# Single_Board_12s_baru_v2.net
KiCad netlist of a schematic drawn in EAGLE
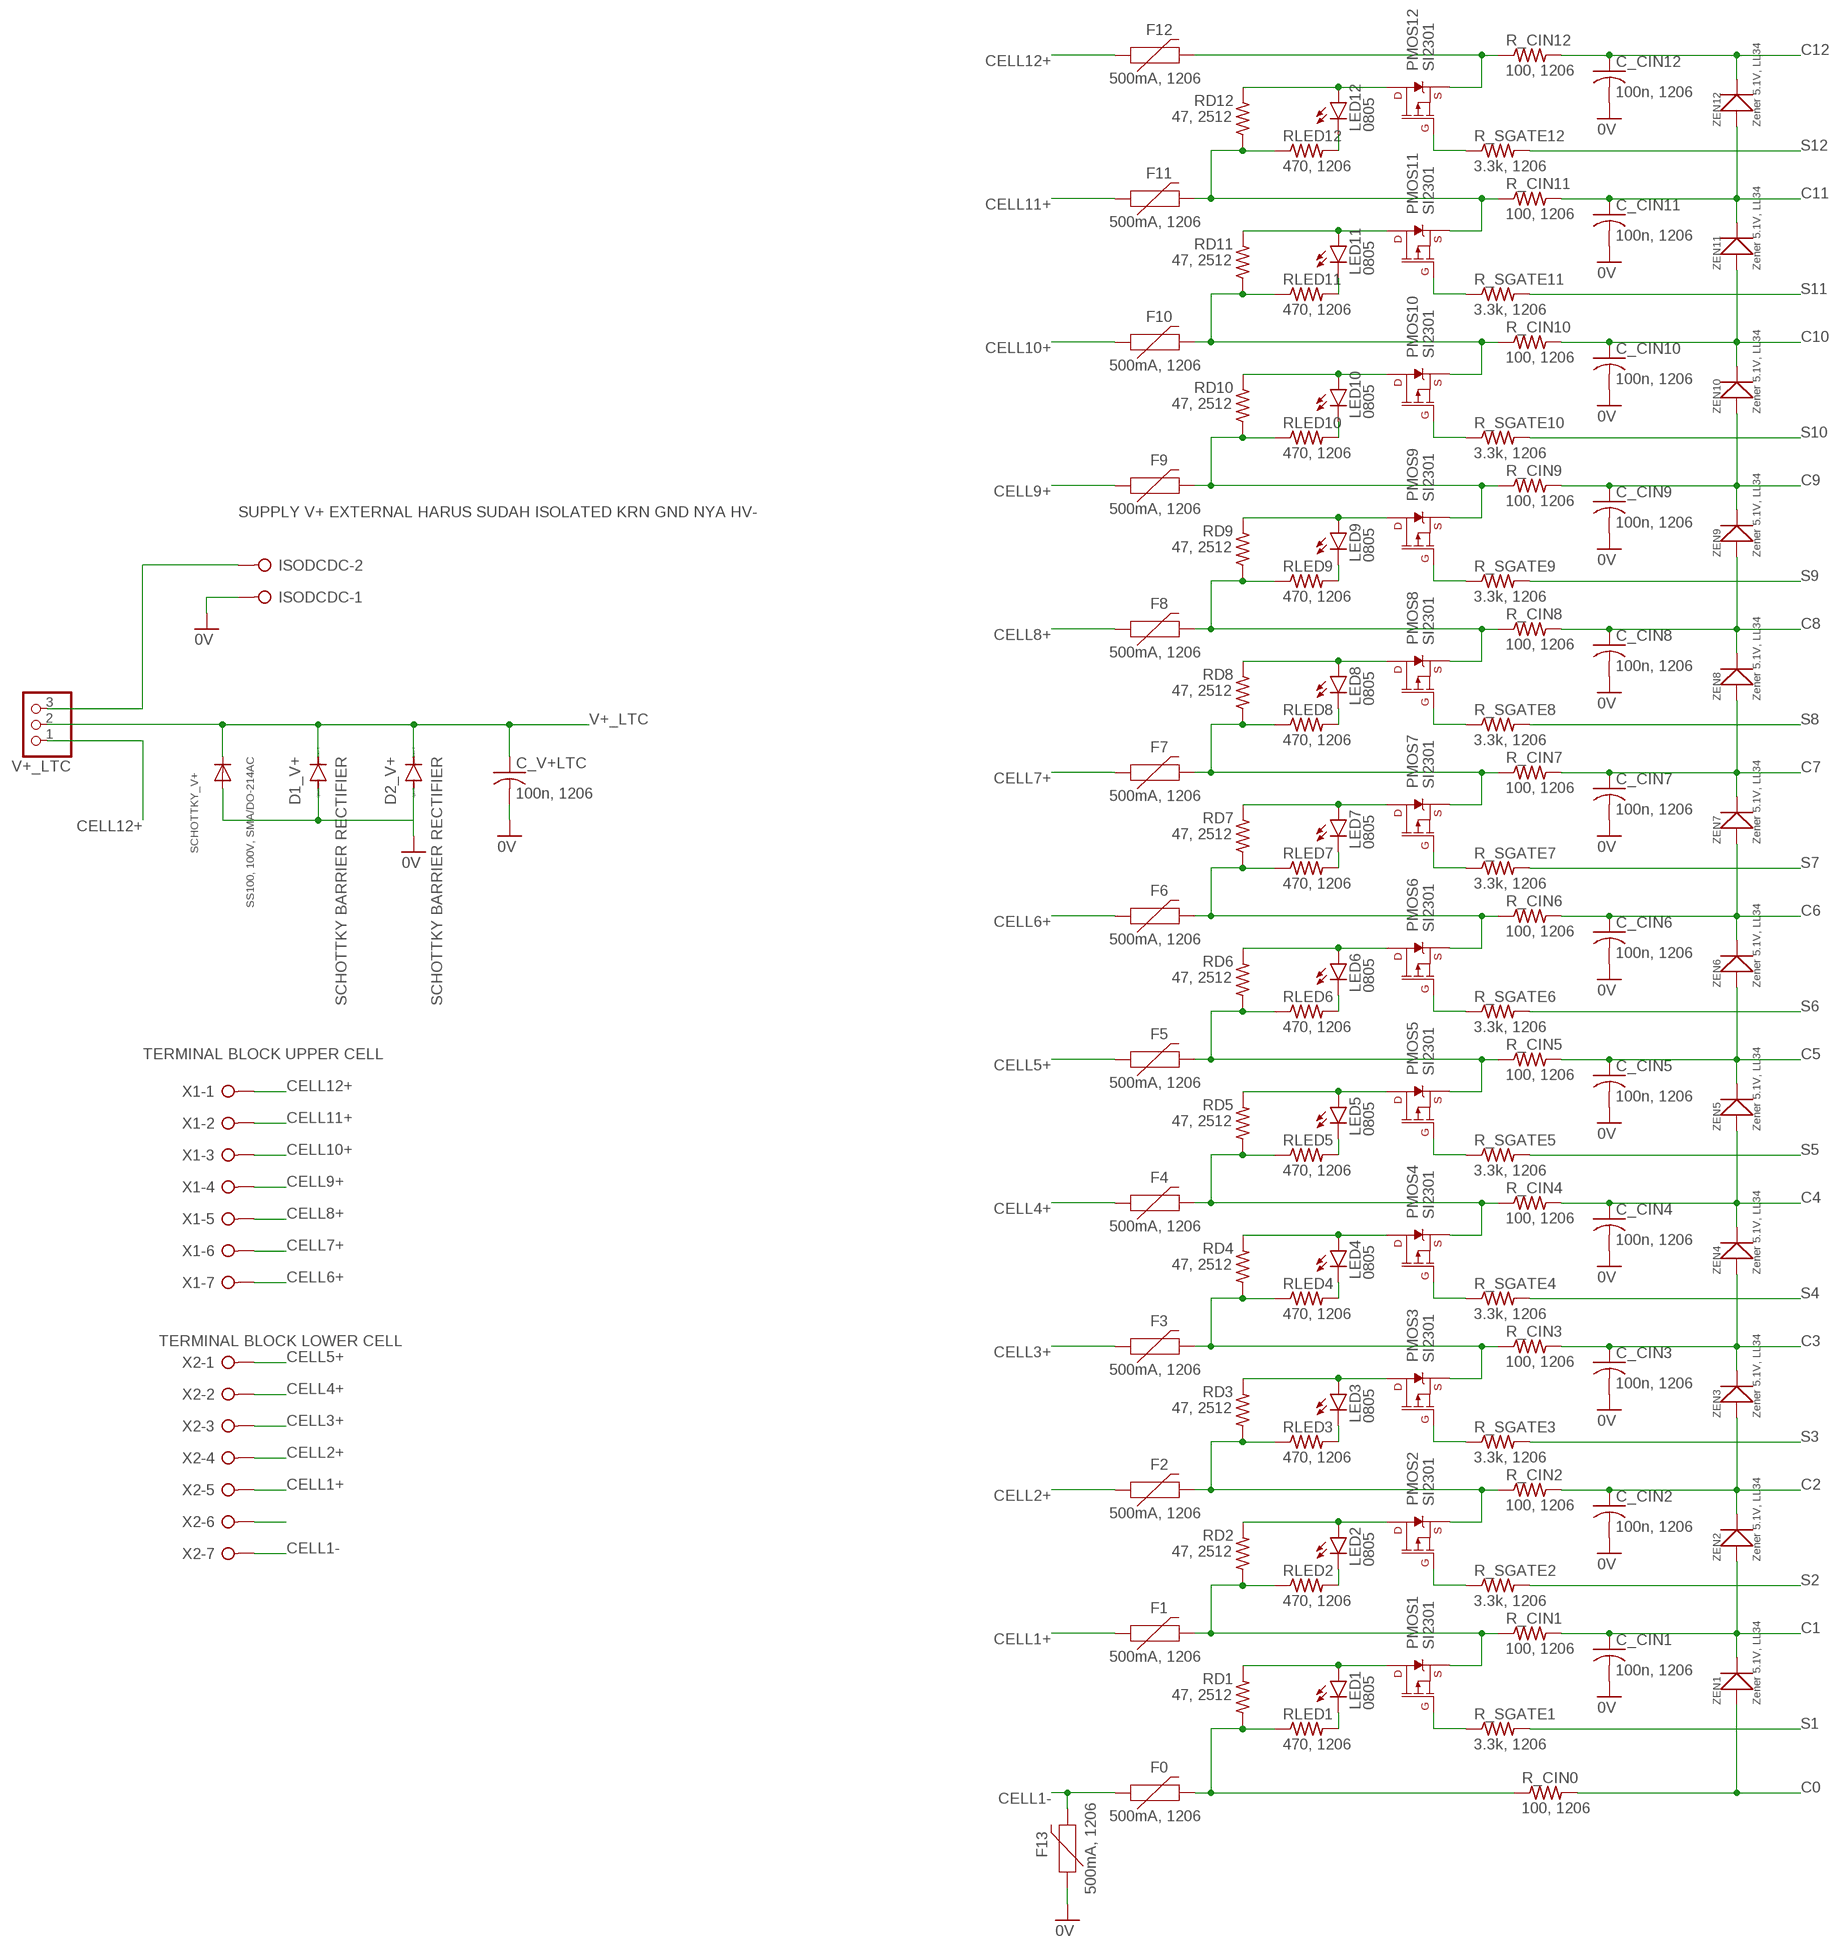
[diagram p0: schematic, sheet 1, part 1 of 2]
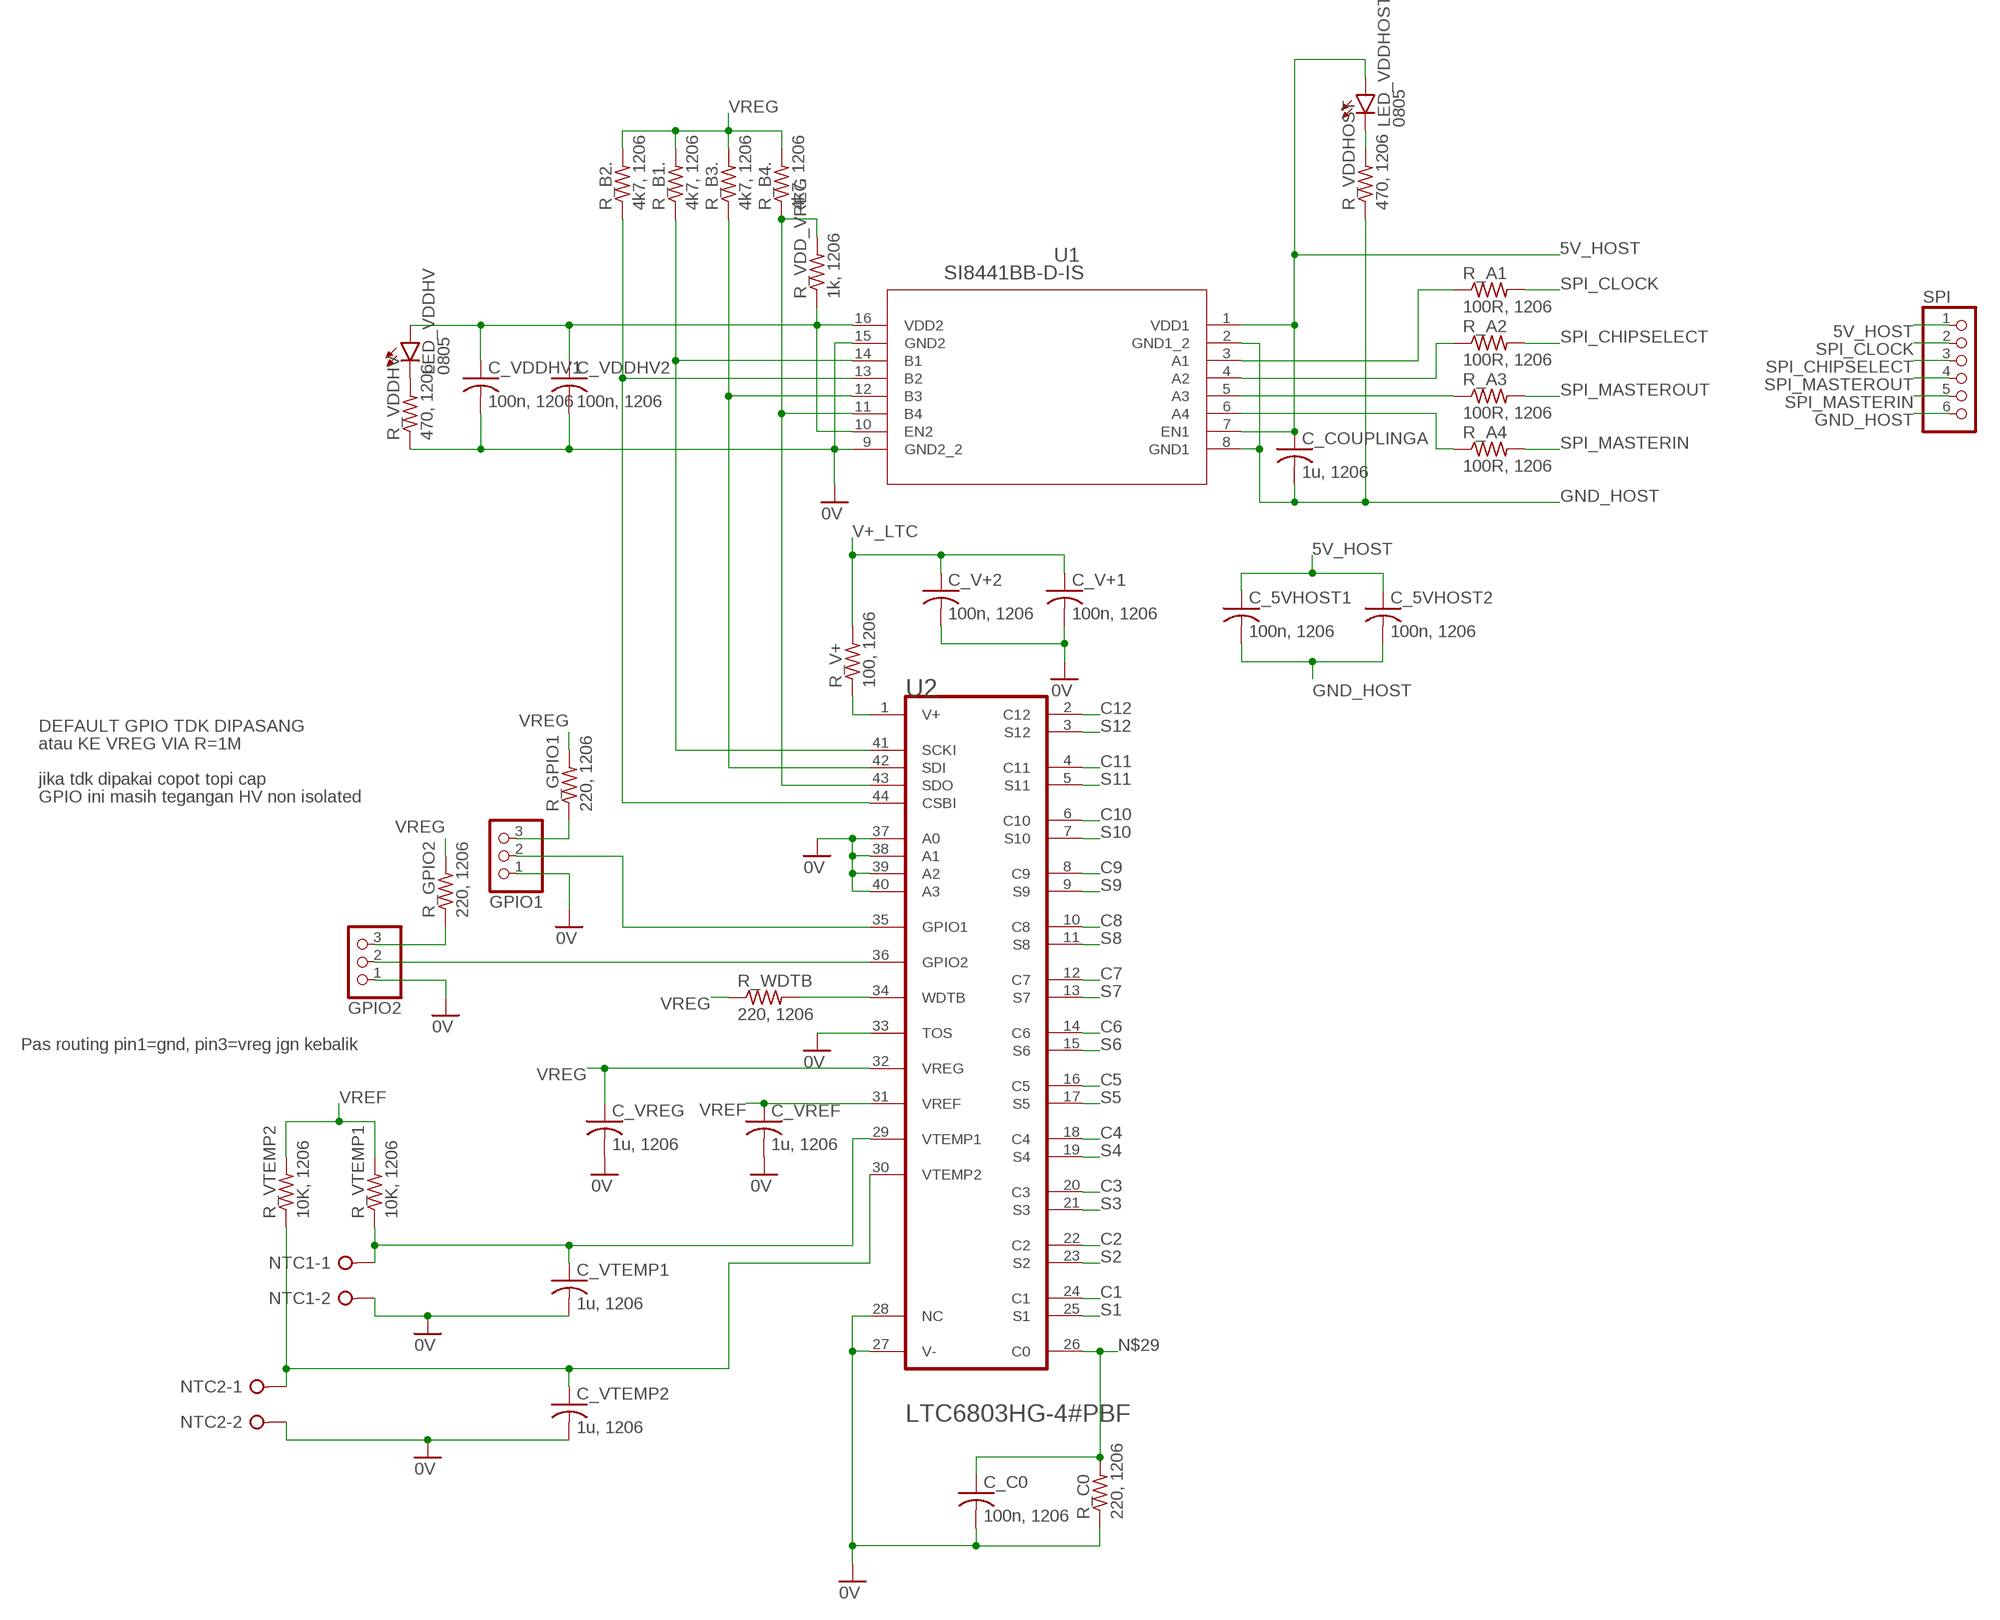
[diagram p1: schematic, sheet 1, part 2 of 2]

(export (version "E")
  (design (tool "Eeschema 10.0.6"))
  (components
    (comp (ref "C_5VHOST1")
      (value "100n, 1206")
      (footprint "eagle-import:C1206")
      (libsource (lib "eagle-import") (part "C-USC1206"))
    )
    (comp (ref "C_5VHOST2")
      (value "100n, 1206")
      (footprint "eagle-import:C1206")
      (libsource (lib "eagle-import") (part "C-USC1206"))
    )
    (comp (ref "C_C0")
      (value "100n, 1206")
      (footprint "eagle-import:C1206")
      (libsource (lib "eagle-import") (part "C-USC1206"))
    )
    (comp (ref "C_CIN1")
      (value "100n, 1206")
      (footprint "eagle-import:C1206")
      (libsource (lib "eagle-import") (part "C-USC1206"))
    )
    (comp (ref "C_CIN2")
      (value "100n, 1206")
      (footprint "eagle-import:C1206")
      (libsource (lib "eagle-import") (part "C-USC1206"))
    )
    (comp (ref "C_CIN3")
      (value "100n, 1206")
      (footprint "eagle-import:C1206")
      (libsource (lib "eagle-import") (part "C-USC1206"))
    )
    (comp (ref "C_CIN4")
      (value "100n, 1206")
      (footprint "eagle-import:C1206")
      (libsource (lib "eagle-import") (part "C-USC1206"))
    )
    (comp (ref "C_CIN5")
      (value "100n, 1206")
      (footprint "eagle-import:C1206")
      (libsource (lib "eagle-import") (part "C-USC1206"))
    )
    (comp (ref "C_CIN6")
      (value "100n, 1206")
      (footprint "eagle-import:C1206")
      (libsource (lib "eagle-import") (part "C-USC1206"))
    )
    (comp (ref "C_CIN7")
      (value "100n, 1206")
      (footprint "eagle-import:C1206")
      (libsource (lib "eagle-import") (part "C-USC1206"))
    )
    (comp (ref "C_CIN8")
      (value "100n, 1206")
      (footprint "eagle-import:C1206")
      (libsource (lib "eagle-import") (part "C-USC1206"))
    )
    (comp (ref "C_CIN9")
      (value "100n, 1206")
      (footprint "eagle-import:C1206")
      (libsource (lib "eagle-import") (part "C-USC1206"))
    )
    (comp (ref "C_CIN10")
      (value "100n, 1206")
      (footprint "eagle-import:C1206")
      (libsource (lib "eagle-import") (part "C-USC1206"))
    )
    (comp (ref "C_CIN11")
      (value "100n, 1206")
      (footprint "eagle-import:C1206")
      (libsource (lib "eagle-import") (part "C-USC1206"))
    )
    (comp (ref "C_CIN12")
      (value "100n, 1206")
      (footprint "eagle-import:C1206")
      (libsource (lib "eagle-import") (part "C-USC1206"))
    )
    (comp (ref "C_COUPLINGA")
      (value "1u, 1206")
      (footprint "eagle-import:C1206")
      (libsource (lib "eagle-import") (part "C-USC1206"))
    )
    (comp (ref "C_V+1")
      (value "100n, 1206")
      (footprint "eagle-import:C1206")
      (libsource (lib "eagle-import") (part "C-USC1206"))
    )
    (comp (ref "C_V+2")
      (value "100n, 1206")
      (footprint "eagle-import:C1206")
      (libsource (lib "eagle-import") (part "C-USC1206"))
    )
    (comp (ref "C_V+LTC")
      (value "100n, 1206")
      (footprint "eagle-import:C1206")
      (libsource (lib "eagle-import") (part "C-USC1206"))
    )
    (comp (ref "C_VDDHV1")
      (value "100n, 1206")
      (footprint "eagle-import:C1206")
      (libsource (lib "eagle-import") (part "C-USC1206"))
    )
    (comp (ref "C_VDDHV2")
      (value "100n, 1206")
      (footprint "eagle-import:C1206")
      (libsource (lib "eagle-import") (part "C-USC1206"))
    )
    (comp (ref "C_VREF")
      (value "1u, 1206")
      (footprint "eagle-import:C1206")
      (libsource (lib "eagle-import") (part "C-USC1206"))
    )
    (comp (ref "C_VREG")
      (value "1u, 1206")
      (footprint "eagle-import:C1206")
      (libsource (lib "eagle-import") (part "C-USC1206"))
    )
    (comp (ref "C_VTEMP1")
      (value "1u, 1206")
      (footprint "eagle-import:C1206")
      (libsource (lib "eagle-import") (part "C-USC1206"))
    )
    (comp (ref "C_VTEMP2")
      (value "1u, 1206")
      (footprint "eagle-import:C1206")
      (libsource (lib "eagle-import") (part "C-USC1206"))
    )
    (comp (ref "D1_V+")
      (value "SCHOTTKY BARRIER RECTIFIER")
      (footprint "eagle-import:DO27-15")
      (libsource (lib "eagle-import") (part "DIODE-DO27-15"))
    )
    (comp (ref "D2_V+")
      (value "SCHOTTKY BARRIER RECTIFIER")
      (footprint "eagle-import:DO27-15")
      (libsource (lib "eagle-import") (part "DIODE-DO27-15"))
    )
    (comp (ref "F0")
      (value "500mA, 1206")
      (footprint "eagle-import:1206")
      (libsource (lib "eagle-import") (part "PPTC_6V500MA-2"))
    )
    (comp (ref "F1")
      (value "500mA, 1206")
      (footprint "eagle-import:1206")
      (libsource (lib "eagle-import") (part "PPTC_6V500MA-2"))
    )
    (comp (ref "F2")
      (value "500mA, 1206")
      (footprint "eagle-import:1206")
      (libsource (lib "eagle-import") (part "PPTC_6V500MA-2"))
    )
    (comp (ref "F3")
      (value "500mA, 1206")
      (footprint "eagle-import:1206")
      (libsource (lib "eagle-import") (part "PPTC_6V500MA-2"))
    )
    (comp (ref "F4")
      (value "500mA, 1206")
      (footprint "eagle-import:1206")
      (libsource (lib "eagle-import") (part "PPTC_6V500MA-2"))
    )
    (comp (ref "F5")
      (value "500mA, 1206")
      (footprint "eagle-import:1206")
      (libsource (lib "eagle-import") (part "PPTC_6V500MA-2"))
    )
    (comp (ref "F6")
      (value "500mA, 1206")
      (footprint "eagle-import:1206")
      (libsource (lib "eagle-import") (part "PPTC_6V500MA-2"))
    )
    (comp (ref "F7")
      (value "500mA, 1206")
      (footprint "eagle-import:1206")
      (libsource (lib "eagle-import") (part "PPTC_6V500MA-2"))
    )
    (comp (ref "F8")
      (value "500mA, 1206")
      (footprint "eagle-import:1206")
      (libsource (lib "eagle-import") (part "PPTC_6V500MA-2"))
    )
    (comp (ref "F9")
      (value "500mA, 1206")
      (footprint "eagle-import:1206")
      (libsource (lib "eagle-import") (part "PPTC_6V500MA-2"))
    )
    (comp (ref "F10")
      (value "500mA, 1206")
      (footprint "eagle-import:1206")
      (libsource (lib "eagle-import") (part "PPTC_6V500MA-2"))
    )
    (comp (ref "F11")
      (value "500mA, 1206")
      (footprint "eagle-import:1206")
      (libsource (lib "eagle-import") (part "PPTC_6V500MA-2"))
    )
    (comp (ref "F12")
      (value "500mA, 1206")
      (footprint "eagle-import:1206")
      (libsource (lib "eagle-import") (part "PPTC_6V500MA-2"))
    )
    (comp (ref "F13")
      (value "500mA, 1206")
      (footprint "eagle-import:1206")
      (libsource (lib "eagle-import") (part "PPTC_6V500MA-2"))
    )
    (comp (ref "GPIO1")
      (value "PINHD-1X3")
      (footprint "eagle-import:1X03")
      (libsource (lib "eagle-import") (part "PINHD-1X3"))
    )
    (comp (ref "GPIO2")
      (value "PINHD-1X3")
      (footprint "eagle-import:1X03")
      (libsource (lib "eagle-import") (part "PINHD-1X3"))
    )
    (comp (ref "ISODCDC")
      (value "W237-02P")
      (footprint "eagle-import:W237-132")
      (libsource (lib "eagle-import") (part "W237-02P"))
    )
    (comp (ref "LED1")
      (value "0805")
      (footprint "eagle-import:SML0805")
      (libsource (lib "eagle-import") (part "LEDSML0805"))
    )
    (comp (ref "LED2")
      (value "0805")
      (footprint "eagle-import:SML0805")
      (libsource (lib "eagle-import") (part "LEDSML0805"))
    )
    (comp (ref "LED3")
      (value "0805")
      (footprint "eagle-import:SML0805")
      (libsource (lib "eagle-import") (part "LEDSML0805"))
    )
    (comp (ref "LED4")
      (value "0805")
      (footprint "eagle-import:SML0805")
      (libsource (lib "eagle-import") (part "LEDSML0805"))
    )
    (comp (ref "LED5")
      (value "0805")
      (footprint "eagle-import:SML0805")
      (libsource (lib "eagle-import") (part "LEDSML0805"))
    )
    (comp (ref "LED6")
      (value "0805")
      (footprint "eagle-import:SML0805")
      (libsource (lib "eagle-import") (part "LEDSML0805"))
    )
    (comp (ref "LED7")
      (value "0805")
      (footprint "eagle-import:SML0805")
      (libsource (lib "eagle-import") (part "LEDSML0805"))
    )
    (comp (ref "LED8")
      (value "0805")
      (footprint "eagle-import:SML0805")
      (libsource (lib "eagle-import") (part "LEDSML0805"))
    )
    (comp (ref "LED9")
      (value "0805")
      (footprint "eagle-import:SML0805")
      (libsource (lib "eagle-import") (part "LEDSML0805"))
    )
    (comp (ref "LED10")
      (value "0805")
      (footprint "eagle-import:SML0805")
      (libsource (lib "eagle-import") (part "LEDSML0805"))
    )
    (comp (ref "LED11")
      (value "0805")
      (footprint "eagle-import:SML0805")
      (libsource (lib "eagle-import") (part "LEDSML0805"))
    )
    (comp (ref "LED12")
      (value "0805")
      (footprint "eagle-import:SML0805")
      (libsource (lib "eagle-import") (part "LEDSML0805"))
    )
    (comp (ref "LED_VDDHOST")
      (value "0805")
      (footprint "eagle-import:SML0805")
      (libsource (lib "eagle-import") (part "LEDSML0805"))
    )
    (comp (ref "LED_VDDHV")
      (value "0805")
      (footprint "eagle-import:SML0805")
      (libsource (lib "eagle-import") (part "LEDSML0805"))
    )
    (comp (ref "NTC1")
      (value "W237-02P")
      (footprint "eagle-import:W237-132")
      (libsource (lib "eagle-import") (part "W237-02P"))
    )
    (comp (ref "NTC2")
      (value "W237-02P")
      (footprint "eagle-import:W237-132")
      (libsource (lib "eagle-import") (part "W237-02P"))
    )
    (comp (ref "PMOS1")
      (value "SI2301")
      (footprint "eagle-import:SOT23-3")
      (libsource (lib "eagle-import") (part "MOSFET_PCH-SI2309DS"))
    )
    (comp (ref "PMOS2")
      (value "SI2301")
      (footprint "eagle-import:SOT23-3")
      (libsource (lib "eagle-import") (part "MOSFET_PCH-SI2309DS"))
    )
    (comp (ref "PMOS3")
      (value "SI2301")
      (footprint "eagle-import:SOT23-3")
      (libsource (lib "eagle-import") (part "MOSFET_PCH-SI2309DS"))
    )
    (comp (ref "PMOS4")
      (value "SI2301")
      (footprint "eagle-import:SOT23-3")
      (libsource (lib "eagle-import") (part "MOSFET_PCH-SI2309DS"))
    )
    (comp (ref "PMOS5")
      (value "SI2301")
      (footprint "eagle-import:SOT23-3")
      (libsource (lib "eagle-import") (part "MOSFET_PCH-SI2309DS"))
    )
    (comp (ref "PMOS6")
      (value "SI2301")
      (footprint "eagle-import:SOT23-3")
      (libsource (lib "eagle-import") (part "MOSFET_PCH-SI2309DS"))
    )
    (comp (ref "PMOS7")
      (value "SI2301")
      (footprint "eagle-import:SOT23-3")
      (libsource (lib "eagle-import") (part "MOSFET_PCH-SI2309DS"))
    )
    (comp (ref "PMOS8")
      (value "SI2301")
      (footprint "eagle-import:SOT23-3")
      (libsource (lib "eagle-import") (part "MOSFET_PCH-SI2309DS"))
    )
    (comp (ref "PMOS9")
      (value "SI2301")
      (footprint "eagle-import:SOT23-3")
      (libsource (lib "eagle-import") (part "MOSFET_PCH-SI2309DS"))
    )
    (comp (ref "PMOS10")
      (value "SI2301")
      (footprint "eagle-import:SOT23-3")
      (libsource (lib "eagle-import") (part "MOSFET_PCH-SI2309DS"))
    )
    (comp (ref "PMOS11")
      (value "SI2301")
      (footprint "eagle-import:SOT23-3")
      (libsource (lib "eagle-import") (part "MOSFET_PCH-SI2309DS"))
    )
    (comp (ref "PMOS12")
      (value "SI2301")
      (footprint "eagle-import:SOT23-3")
      (libsource (lib "eagle-import") (part "MOSFET_PCH-SI2309DS"))
    )
    (comp (ref "RD1")
      (value "47, 2512")
      (footprint "eagle-import:R2512")
      (libsource (lib "eagle-import") (part "R-US_R2512"))
    )
    (comp (ref "RD2")
      (value "47, 2512")
      (footprint "eagle-import:R2512")
      (libsource (lib "eagle-import") (part "R-US_R2512"))
    )
    (comp (ref "RD3")
      (value "47, 2512")
      (footprint "eagle-import:R2512")
      (libsource (lib "eagle-import") (part "R-US_R2512"))
    )
    (comp (ref "RD4")
      (value "47, 2512")
      (footprint "eagle-import:R2512")
      (libsource (lib "eagle-import") (part "R-US_R2512"))
    )
    (comp (ref "RD5")
      (value "47, 2512")
      (footprint "eagle-import:R2512")
      (libsource (lib "eagle-import") (part "R-US_R2512"))
    )
    (comp (ref "RD6")
      (value "47, 2512")
      (footprint "eagle-import:R2512")
      (libsource (lib "eagle-import") (part "R-US_R2512"))
    )
    (comp (ref "RD7")
      (value "47, 2512")
      (footprint "eagle-import:R2512")
      (libsource (lib "eagle-import") (part "R-US_R2512"))
    )
    (comp (ref "RD8")
      (value "47, 2512")
      (footprint "eagle-import:R2512")
      (libsource (lib "eagle-import") (part "R-US_R2512"))
    )
    (comp (ref "RD9")
      (value "47, 2512")
      (footprint "eagle-import:R2512")
      (libsource (lib "eagle-import") (part "R-US_R2512"))
    )
    (comp (ref "RD10")
      (value "47, 2512")
      (footprint "eagle-import:R2512")
      (libsource (lib "eagle-import") (part "R-US_R2512"))
    )
    (comp (ref "RD11")
      (value "47, 2512")
      (footprint "eagle-import:R2512")
      (libsource (lib "eagle-import") (part "R-US_R2512"))
    )
    (comp (ref "RD12")
      (value "47, 2512")
      (footprint "eagle-import:R2512")
      (libsource (lib "eagle-import") (part "R-US_R2512"))
    )
    (comp (ref "RLED1")
      (value "470, 1206")
      (footprint "eagle-import:R1206")
      (libsource (lib "eagle-import") (part "R-US_R1206"))
    )
    (comp (ref "RLED2")
      (value "470, 1206")
      (footprint "eagle-import:R1206")
      (libsource (lib "eagle-import") (part "R-US_R1206"))
    )
    (comp (ref "RLED3")
      (value "470, 1206")
      (footprint "eagle-import:R1206")
      (libsource (lib "eagle-import") (part "R-US_R1206"))
    )
    (comp (ref "RLED4")
      (value "470, 1206")
      (footprint "eagle-import:R1206")
      (libsource (lib "eagle-import") (part "R-US_R1206"))
    )
    (comp (ref "RLED5")
      (value "470, 1206")
      (footprint "eagle-import:R1206")
      (libsource (lib "eagle-import") (part "R-US_R1206"))
    )
    (comp (ref "RLED6")
      (value "470, 1206")
      (footprint "eagle-import:R1206")
      (libsource (lib "eagle-import") (part "R-US_R1206"))
    )
    (comp (ref "RLED7")
      (value "470, 1206")
      (footprint "eagle-import:R1206")
      (libsource (lib "eagle-import") (part "R-US_R1206"))
    )
    (comp (ref "RLED8")
      (value "470, 1206")
      (footprint "eagle-import:R1206")
      (libsource (lib "eagle-import") (part "R-US_R1206"))
    )
    (comp (ref "RLED9")
      (value "470, 1206")
      (footprint "eagle-import:R1206")
      (libsource (lib "eagle-import") (part "R-US_R1206"))
    )
    (comp (ref "RLED10")
      (value "470, 1206")
      (footprint "eagle-import:R1206")
      (libsource (lib "eagle-import") (part "R-US_R1206"))
    )
    (comp (ref "RLED11")
      (value "470, 1206")
      (footprint "eagle-import:R1206")
      (libsource (lib "eagle-import") (part "R-US_R1206"))
    )
    (comp (ref "RLED12")
      (value "470, 1206")
      (footprint "eagle-import:R1206")
      (libsource (lib "eagle-import") (part "R-US_R1206"))
    )
    (comp (ref "R_A1")
      (value "100R, 1206")
      (footprint "eagle-import:R1206")
      (libsource (lib "eagle-import") (part "R-US_R1206"))
    )
    (comp (ref "R_A2")
      (value "100R, 1206")
      (footprint "eagle-import:R1206")
      (libsource (lib "eagle-import") (part "R-US_R1206"))
    )
    (comp (ref "R_A3")
      (value "100R, 1206")
      (footprint "eagle-import:R1206")
      (libsource (lib "eagle-import") (part "R-US_R1206"))
    )
    (comp (ref "R_A4")
      (value "100R, 1206")
      (footprint "eagle-import:R1206")
      (libsource (lib "eagle-import") (part "R-US_R1206"))
    )
    (comp (ref "R_B1.")
      (value "4k7, 1206")
      (footprint "eagle-import:R1206")
      (libsource (lib "eagle-import") (part "R-US_R1206"))
    )
    (comp (ref "R_B2.")
      (value "4k7, 1206")
      (footprint "eagle-import:R1206")
      (libsource (lib "eagle-import") (part "R-US_R1206"))
    )
    (comp (ref "R_B3.")
      (value "4k7, 1206")
      (footprint "eagle-import:R1206")
      (libsource (lib "eagle-import") (part "R-US_R1206"))
    )
    (comp (ref "R_B4.")
      (value "4k7, 1206")
      (footprint "eagle-import:R1206")
      (libsource (lib "eagle-import") (part "R-US_R1206"))
    )
    (comp (ref "R_C0")
      (value "220, 1206")
      (footprint "eagle-import:R1206")
      (libsource (lib "eagle-import") (part "R-US_R1206"))
    )
    (comp (ref "R_CIN0")
      (value "100, 1206")
      (footprint "eagle-import:R1206")
      (libsource (lib "eagle-import") (part "R-US_R1206"))
    )
    (comp (ref "R_CIN1")
      (value "100, 1206")
      (footprint "eagle-import:R1206")
      (libsource (lib "eagle-import") (part "R-US_R1206"))
    )
    (comp (ref "R_CIN2")
      (value "100, 1206")
      (footprint "eagle-import:R1206")
      (libsource (lib "eagle-import") (part "R-US_R1206"))
    )
    (comp (ref "R_CIN3")
      (value "100, 1206")
      (footprint "eagle-import:R1206")
      (libsource (lib "eagle-import") (part "R-US_R1206"))
    )
    (comp (ref "R_CIN4")
      (value "100, 1206")
      (footprint "eagle-import:R1206")
      (libsource (lib "eagle-import") (part "R-US_R1206"))
    )
    (comp (ref "R_CIN5")
      (value "100, 1206")
      (footprint "eagle-import:R1206")
      (libsource (lib "eagle-import") (part "R-US_R1206"))
    )
    (comp (ref "R_CIN6")
      (value "100, 1206")
      (footprint "eagle-import:R1206")
      (libsource (lib "eagle-import") (part "R-US_R1206"))
    )
    (comp (ref "R_CIN7")
      (value "100, 1206")
      (footprint "eagle-import:R1206")
      (libsource (lib "eagle-import") (part "R-US_R1206"))
    )
    (comp (ref "R_CIN8")
      (value "100, 1206")
      (footprint "eagle-import:R1206")
      (libsource (lib "eagle-import") (part "R-US_R1206"))
    )
    (comp (ref "R_CIN9")
      (value "100, 1206")
      (footprint "eagle-import:R1206")
      (libsource (lib "eagle-import") (part "R-US_R1206"))
    )
    (comp (ref "R_CIN10")
      (value "100, 1206")
      (footprint "eagle-import:R1206")
      (libsource (lib "eagle-import") (part "R-US_R1206"))
    )
    (comp (ref "R_CIN11")
      (value "100, 1206")
      (footprint "eagle-import:R1206")
      (libsource (lib "eagle-import") (part "R-US_R1206"))
    )
    (comp (ref "R_CIN12")
      (value "100, 1206")
      (footprint "eagle-import:R1206")
      (libsource (lib "eagle-import") (part "R-US_R1206"))
    )
    (comp (ref "R_GPIO1")
      (value "220, 1206")
      (footprint "eagle-import:R1206")
      (libsource (lib "eagle-import") (part "R-US_R1206"))
    )
    (comp (ref "R_GPIO2")
      (value "220, 1206")
      (footprint "eagle-import:R1206")
      (libsource (lib "eagle-import") (part "R-US_R1206"))
    )
    (comp (ref "R_SGATE1")
      (value "3.3k, 1206")
      (footprint "eagle-import:R1206")
      (libsource (lib "eagle-import") (part "R-US_R1206"))
    )
    (comp (ref "R_SGATE2")
      (value "3.3k, 1206")
      (footprint "eagle-import:R1206")
      (libsource (lib "eagle-import") (part "R-US_R1206"))
    )
    (comp (ref "R_SGATE3")
      (value "3.3k, 1206")
      (footprint "eagle-import:R1206")
      (libsource (lib "eagle-import") (part "R-US_R1206"))
    )
    (comp (ref "R_SGATE4")
      (value "3.3k, 1206")
      (footprint "eagle-import:R1206")
      (libsource (lib "eagle-import") (part "R-US_R1206"))
    )
    (comp (ref "R_SGATE5")
      (value "3.3k, 1206")
      (footprint "eagle-import:R1206")
      (libsource (lib "eagle-import") (part "R-US_R1206"))
    )
    (comp (ref "R_SGATE6")
      (value "3.3k, 1206")
      (footprint "eagle-import:R1206")
      (libsource (lib "eagle-import") (part "R-US_R1206"))
    )
    (comp (ref "R_SGATE7")
      (value "3.3k, 1206")
      (footprint "eagle-import:R1206")
      (libsource (lib "eagle-import") (part "R-US_R1206"))
    )
    (comp (ref "R_SGATE8")
      (value "3.3k, 1206")
      (footprint "eagle-import:R1206")
      (libsource (lib "eagle-import") (part "R-US_R1206"))
    )
    (comp (ref "R_SGATE9")
      (value "3.3k, 1206")
      (footprint "eagle-import:R1206")
      (libsource (lib "eagle-import") (part "R-US_R1206"))
    )
    (comp (ref "R_SGATE10")
      (value "3.3k, 1206")
      (footprint "eagle-import:R1206")
      (libsource (lib "eagle-import") (part "R-US_R1206"))
    )
    (comp (ref "R_SGATE11")
      (value "3.3k, 1206")
      (footprint "eagle-import:R1206")
      (libsource (lib "eagle-import") (part "R-US_R1206"))
    )
    (comp (ref "R_SGATE12")
      (value "3.3k, 1206")
      (footprint "eagle-import:R1206")
      (libsource (lib "eagle-import") (part "R-US_R1206"))
    )
    (comp (ref "R_V+")
      (value "100, 1206")
      (footprint "eagle-import:R1206")
      (libsource (lib "eagle-import") (part "R-US_R1206"))
    )
    (comp (ref "R_VDDHOST")
      (value "470, 1206")
      (footprint "eagle-import:R1206")
      (libsource (lib "eagle-import") (part "R-US_R1206"))
    )
    (comp (ref "R_VDDHV")
      (value "470, 1206")
      (footprint "eagle-import:R1206")
      (libsource (lib "eagle-import") (part "R-US_R1206"))
    )
    (comp (ref "R_VDD_VREG")
      (value "1k, 1206")
      (footprint "eagle-import:R1206")
      (libsource (lib "eagle-import") (part "R-US_R1206"))
    )
    (comp (ref "R_VTEMP1")
      (value "10K, 1206")
      (footprint "eagle-import:R1206")
      (libsource (lib "eagle-import") (part "R-US_R1206"))
    )
    (comp (ref "R_VTEMP2")
      (value "10K, 1206")
      (footprint "eagle-import:R1206")
      (libsource (lib "eagle-import") (part "R-US_R1206"))
    )
    (comp (ref "R_WDTB")
      (value "220, 1206")
      (footprint "eagle-import:R1206")
      (libsource (lib "eagle-import") (part "R-US_R1206"))
    )
    (comp (ref "SCHOTTKY_V+")
      (value "SS100, 100V, SMA/DO-214AC")
      (footprint "eagle-import:SMADIODE")
      (libsource (lib "eagle-import") (part "DIODESMA"))
    )
    (comp (ref "SPI")
      (value "PINHD-1X6")
      (footprint "eagle-import:1X06")
      (libsource (lib "eagle-import") (part "PINHD-1X6"))
    )
    (comp (ref "U1")
      (value "SI8441BB-D-IS")
      (footprint "eagle-import:SOIC-16W_SIL")
      (fields (field (name "COPYRIGHT") "Copyright (C) 2021 Ultra Librarian. All rights reserved."))
      (libsource (lib "eagle-import") (part "SI8441BB-D-IS"))
    )
    (comp (ref "U2")
      (value "LINEAR_TECHNOLOGY_LTC6803HG-4#PBFLINEAR_TECHNOLOGY_LTC6803HG-4#PBF_0_2")
      (footprint "eagle-import:LINEAR_TECHNOLOGY_LTC6803HG-4#PBF_2")
      (fields (field (name "MF") "Linear Technology") (field (name "MPN") "LTC6803HG-4#PBF"))
      (libsource (lib "eagle-import") (part "LINEAR_TECHNOLOGY_LTC6803HG-4#PBFLINEAR_TECHNOLOGY_LTC6803HG-4#PBF_0_2"))
    )
    (comp (ref "V+_LTC")
      (value "PINHD-1X3")
      (footprint "eagle-import:1X03")
      (libsource (lib "eagle-import") (part "PINHD-1X3"))
    )
    (comp (ref "X1")
      (value "W237-07P")
      (footprint "eagle-import:W237-7P")
      (libsource (lib "eagle-import") (part "W237-07P"))
    )
    (comp (ref "X2")
      (value "W237-07P")
      (footprint "eagle-import:W237-7P")
      (libsource (lib "eagle-import") (part "W237-07P"))
    )
    (comp (ref "ZEN1")
      (value "Zener 5.1V, LL34")
      (footprint "eagle-import:LL-34")
      (fields (field (name "MPN") "LL4148ST"))
      (libsource (lib "eagle-import") (part "SMD-DIODE-SWITCHING-75V-200MA(LL-34)"))
    )
    (comp (ref "ZEN2")
      (value "Zener 5.1V, LL34")
      (footprint "eagle-import:LL-34")
      (fields (field (name "MPN") "LL4148ST"))
      (libsource (lib "eagle-import") (part "SMD-DIODE-SWITCHING-75V-200MA(LL-34)"))
    )
    (comp (ref "ZEN3")
      (value "Zener 5.1V, LL34")
      (footprint "eagle-import:LL-34")
      (fields (field (name "MPN") "LL4148ST"))
      (libsource (lib "eagle-import") (part "SMD-DIODE-SWITCHING-75V-200MA(LL-34)"))
    )
    (comp (ref "ZEN4")
      (value "Zener 5.1V, LL34")
      (footprint "eagle-import:LL-34")
      (fields (field (name "MPN") "LL4148ST"))
      (libsource (lib "eagle-import") (part "SMD-DIODE-SWITCHING-75V-200MA(LL-34)"))
    )
    (comp (ref "ZEN5")
      (value "Zener 5.1V, LL34")
      (footprint "eagle-import:LL-34")
      (fields (field (name "MPN") "LL4148ST"))
      (libsource (lib "eagle-import") (part "SMD-DIODE-SWITCHING-75V-200MA(LL-34)"))
    )
    (comp (ref "ZEN6")
      (value "Zener 5.1V, LL34")
      (footprint "eagle-import:LL-34")
      (fields (field (name "MPN") "LL4148ST"))
      (libsource (lib "eagle-import") (part "SMD-DIODE-SWITCHING-75V-200MA(LL-34)"))
    )
    (comp (ref "ZEN7")
      (value "Zener 5.1V, LL34")
      (footprint "eagle-import:LL-34")
      (fields (field (name "MPN") "LL4148ST"))
      (libsource (lib "eagle-import") (part "SMD-DIODE-SWITCHING-75V-200MA(LL-34)"))
    )
    (comp (ref "ZEN8")
      (value "Zener 5.1V, LL34")
      (footprint "eagle-import:LL-34")
      (fields (field (name "MPN") "LL4148ST"))
      (libsource (lib "eagle-import") (part "SMD-DIODE-SWITCHING-75V-200MA(LL-34)"))
    )
    (comp (ref "ZEN9")
      (value "Zener 5.1V, LL34")
      (footprint "eagle-import:LL-34")
      (fields (field (name "MPN") "LL4148ST"))
      (libsource (lib "eagle-import") (part "SMD-DIODE-SWITCHING-75V-200MA(LL-34)"))
    )
    (comp (ref "ZEN10")
      (value "Zener 5.1V, LL34")
      (footprint "eagle-import:LL-34")
      (fields (field (name "MPN") "LL4148ST"))
      (libsource (lib "eagle-import") (part "SMD-DIODE-SWITCHING-75V-200MA(LL-34)"))
    )
    (comp (ref "ZEN11")
      (value "Zener 5.1V, LL34")
      (footprint "eagle-import:LL-34")
      (fields (field (name "MPN") "LL4148ST"))
      (libsource (lib "eagle-import") (part "SMD-DIODE-SWITCHING-75V-200MA(LL-34)"))
    )
    (comp (ref "ZEN12")
      (value "Zener 5.1V, LL34")
      (footprint "eagle-import:LL-34")
      (fields (field (name "MPN") "LL4148ST"))
      (libsource (lib "eagle-import") (part "SMD-DIODE-SWITCHING-75V-200MA(LL-34)"))
    )
  )
  (nets
    (net (code "1") (name "/5V_HOST") (class "Default")
      (node (ref "C_5VHOST1") (pin "1") (pinfunction "1_1") (pintype "passive"))
      (node (ref "C_5VHOST2") (pin "1") (pinfunction "1_1") (pintype "passive"))
      (node (ref "C_COUPLINGA") (pin "1") (pinfunction "1_1") (pintype "passive"))
      (node (ref "LED_VDDHOST") (pin "A") (pinfunction "A_A") (pintype "passive"))
      (node (ref "SPI") (pin "1") (pinfunction "1_1") (pintype "passive"))
      (node (ref "U1") (pin "1") (pinfunction "VDD1_1") (pintype "passive"))
      (node (ref "U1") (pin "7") (pinfunction "EN1_7") (pintype "input"))
    )
    (net (code "2") (name "/C0") (class "Default")
      (node (ref "R_CIN0") (pin "2") (pinfunction "2_2") (pintype "passive"))
      (node (ref "ZEN1") (pin "A") (pinfunction "+_A") (pintype "passive"))
    )
    (net (code "3") (name "/C1") (class "Default")
      (node (ref "C_CIN1") (pin "1") (pinfunction "1_1") (pintype "passive"))
      (node (ref "R_CIN1") (pin "2") (pinfunction "2_2") (pintype "passive"))
      (node (ref "U2") (pin "24") (pinfunction "C1_24") (pintype "input"))
      (node (ref "ZEN1") (pin "C") (pinfunction "-_C") (pintype "passive"))
      (node (ref "ZEN2") (pin "A") (pinfunction "+_A") (pintype "passive"))
    )
    (net (code "4") (name "/C2") (class "Default")
      (node (ref "C_CIN2") (pin "1") (pinfunction "1_1") (pintype "passive"))
      (node (ref "R_CIN2") (pin "2") (pinfunction "2_2") (pintype "passive"))
      (node (ref "U2") (pin "22") (pinfunction "C2_22") (pintype "input"))
      (node (ref "ZEN2") (pin "C") (pinfunction "-_C") (pintype "passive"))
      (node (ref "ZEN3") (pin "A") (pinfunction "+_A") (pintype "passive"))
    )
    (net (code "5") (name "/C3") (class "Default")
      (node (ref "C_CIN3") (pin "1") (pinfunction "1_1") (pintype "passive"))
      (node (ref "R_CIN3") (pin "2") (pinfunction "2_2") (pintype "passive"))
      (node (ref "U2") (pin "20") (pinfunction "C3_20") (pintype "input"))
      (node (ref "ZEN3") (pin "C") (pinfunction "-_C") (pintype "passive"))
      (node (ref "ZEN4") (pin "A") (pinfunction "+_A") (pintype "passive"))
    )
    (net (code "6") (name "/C4") (class "Default")
      (node (ref "C_CIN4") (pin "1") (pinfunction "1_1") (pintype "passive"))
      (node (ref "R_CIN4") (pin "2") (pinfunction "2_2") (pintype "passive"))
      (node (ref "U2") (pin "18") (pinfunction "C4_18") (pintype "input"))
      (node (ref "ZEN4") (pin "C") (pinfunction "-_C") (pintype "passive"))
      (node (ref "ZEN5") (pin "A") (pinfunction "+_A") (pintype "passive"))
    )
    (net (code "7") (name "/C5") (class "Default")
      (node (ref "C_CIN5") (pin "1") (pinfunction "1_1") (pintype "passive"))
      (node (ref "R_CIN5") (pin "2") (pinfunction "2_2") (pintype "passive"))
      (node (ref "U2") (pin "16") (pinfunction "C5_16") (pintype "input"))
      (node (ref "ZEN5") (pin "C") (pinfunction "-_C") (pintype "passive"))
      (node (ref "ZEN6") (pin "A") (pinfunction "+_A") (pintype "passive"))
    )
    (net (code "8") (name "/C6") (class "Default")
      (node (ref "C_CIN6") (pin "1") (pinfunction "1_1") (pintype "passive"))
      (node (ref "R_CIN6") (pin "2") (pinfunction "2_2") (pintype "passive"))
      (node (ref "U2") (pin "14") (pinfunction "C6_14") (pintype "input"))
      (node (ref "ZEN6") (pin "C") (pinfunction "-_C") (pintype "passive"))
      (node (ref "ZEN7") (pin "A") (pinfunction "+_A") (pintype "passive"))
    )
    (net (code "9") (name "/C7") (class "Default")
      (node (ref "C_CIN7") (pin "1") (pinfunction "1_1") (pintype "passive"))
      (node (ref "R_CIN7") (pin "2") (pinfunction "2_2") (pintype "passive"))
      (node (ref "U2") (pin "12") (pinfunction "C7_12") (pintype "input"))
      (node (ref "ZEN7") (pin "C") (pinfunction "-_C") (pintype "passive"))
      (node (ref "ZEN8") (pin "A") (pinfunction "+_A") (pintype "passive"))
    )
    (net (code "10") (name "/C8") (class "Default")
      (node (ref "C_CIN8") (pin "1") (pinfunction "1_1") (pintype "passive"))
      (node (ref "R_CIN8") (pin "2") (pinfunction "2_2") (pintype "passive"))
      (node (ref "U2") (pin "10") (pinfunction "C8_10") (pintype "input"))
      (node (ref "ZEN8") (pin "C") (pinfunction "-_C") (pintype "passive"))
      (node (ref "ZEN9") (pin "A") (pinfunction "+_A") (pintype "passive"))
    )
    (net (code "11") (name "/C9") (class "Default")
      (node (ref "C_CIN9") (pin "1") (pinfunction "1_1") (pintype "passive"))
      (node (ref "R_CIN9") (pin "2") (pinfunction "2_2") (pintype "passive"))
      (node (ref "U2") (pin "8") (pinfunction "C9_8") (pintype "input"))
      (node (ref "ZEN10") (pin "A") (pinfunction "+_A") (pintype "passive"))
      (node (ref "ZEN9") (pin "C") (pinfunction "-_C") (pintype "passive"))
    )
    (net (code "12") (name "/C10") (class "Default")
      (node (ref "C_CIN10") (pin "1") (pinfunction "1_1") (pintype "passive"))
      (node (ref "R_CIN10") (pin "2") (pinfunction "2_2") (pintype "passive"))
      (node (ref "U2") (pin "6") (pinfunction "C10_6") (pintype "input"))
      (node (ref "ZEN10") (pin "C") (pinfunction "-_C") (pintype "passive"))
      (node (ref "ZEN11") (pin "A") (pinfunction "+_A") (pintype "passive"))
    )
    (net (code "13") (name "/C11") (class "Default")
      (node (ref "C_CIN11") (pin "1") (pinfunction "1_1") (pintype "passive"))
      (node (ref "R_CIN11") (pin "2") (pinfunction "2_2") (pintype "passive"))
      (node (ref "U2") (pin "4") (pinfunction "C11_4") (pintype "input"))
      (node (ref "ZEN11") (pin "C") (pinfunction "-_C") (pintype "passive"))
      (node (ref "ZEN12") (pin "A") (pinfunction "+_A") (pintype "passive"))
    )
    (net (code "14") (name "/C12") (class "Default")
      (node (ref "C_CIN12") (pin "1") (pinfunction "1_1") (pintype "passive"))
      (node (ref "R_CIN12") (pin "2") (pinfunction "2_2") (pintype "passive"))
      (node (ref "U2") (pin "2") (pinfunction "C12_2") (pintype "input"))
      (node (ref "ZEN12") (pin "C") (pinfunction "-_C") (pintype "passive"))
    )
    (net (code "15") (name "/CELL1+") (class "Default")
      (node (ref "F1") (pin "1") (pinfunction "1_1") (pintype "bidirectional"))
      (node (ref "X2") (pin "5") (pinfunction "KL_5") (pintype "passive"))
    )
    (net (code "16") (name "/CELL1-") (class "Default")
      (node (ref "F0") (pin "1") (pinfunction "1_1") (pintype "bidirectional"))
      (node (ref "F13") (pin "2") (pinfunction "2_2") (pintype "bidirectional"))
      (node (ref "X2") (pin "7") (pinfunction "KL_7") (pintype "passive"))
    )
    (net (code "17") (name "/CELL2+") (class "Default")
      (node (ref "F2") (pin "1") (pinfunction "1_1") (pintype "bidirectional"))
      (node (ref "X2") (pin "4") (pinfunction "KL_4") (pintype "passive"))
    )
    (net (code "18") (name "/CELL3+") (class "Default")
      (node (ref "F3") (pin "1") (pinfunction "1_1") (pintype "bidirectional"))
      (node (ref "X2") (pin "3") (pinfunction "KL_3") (pintype "passive"))
    )
    (net (code "19") (name "/CELL4+") (class "Default")
      (node (ref "F4") (pin "1") (pinfunction "1_1") (pintype "bidirectional"))
      (node (ref "X2") (pin "2") (pinfunction "KL_2") (pintype "passive"))
    )
    (net (code "20") (name "/CELL5+") (class "Default")
      (node (ref "F5") (pin "1") (pinfunction "1_1") (pintype "bidirectional"))
      (node (ref "X2") (pin "1") (pinfunction "KL_1") (pintype "passive"))
    )
    (net (code "21") (name "/CELL6+") (class "Default")
      (node (ref "F6") (pin "1") (pinfunction "1_1") (pintype "bidirectional"))
      (node (ref "X1") (pin "7") (pinfunction "KL_7") (pintype "passive"))
    )
    (net (code "22") (name "/CELL7+") (class "Default")
      (node (ref "F7") (pin "1") (pinfunction "1_1") (pintype "bidirectional"))
      (node (ref "X1") (pin "6") (pinfunction "KL_6") (pintype "passive"))
    )
    (net (code "23") (name "/CELL8+") (class "Default")
      (node (ref "F8") (pin "1") (pinfunction "1_1") (pintype "bidirectional"))
      (node (ref "X1") (pin "5") (pinfunction "KL_5") (pintype "passive"))
    )
    (net (code "24") (name "/CELL9+") (class "Default")
      (node (ref "F9") (pin "1") (pinfunction "1_1") (pintype "bidirectional"))
      (node (ref "X1") (pin "4") (pinfunction "KL_4") (pintype "passive"))
    )
    (net (code "25") (name "/CELL10+") (class "Default")
      (node (ref "F10") (pin "1") (pinfunction "1_1") (pintype "bidirectional"))
      (node (ref "X1") (pin "3") (pinfunction "KL_3") (pintype "passive"))
    )
    (net (code "26") (name "/CELL11+") (class "Default")
      (node (ref "F11") (pin "1") (pinfunction "1_1") (pintype "bidirectional"))
      (node (ref "X1") (pin "2") (pinfunction "KL_2") (pintype "passive"))
    )
    (net (code "27") (name "/CELL12+") (class "Default")
      (node (ref "F12") (pin "1") (pinfunction "1_1") (pintype "bidirectional"))
      (node (ref "V+_LTC") (pin "1") (pinfunction "1_1") (pintype "passive"))
      (node (ref "X1") (pin "1") (pinfunction "KL_1") (pintype "passive"))
    )
    (net (code "28") (name "/GND_HOST") (class "Default")
      (node (ref "C_5VHOST1") (pin "2") (pinfunction "2_2") (pintype "passive"))
      (node (ref "C_5VHOST2") (pin "2") (pinfunction "2_2") (pintype "passive"))
      (node (ref "C_COUPLINGA") (pin "2") (pinfunction "2_2") (pintype "passive"))
      (node (ref "R_VDDHOST") (pin "1") (pinfunction "1_1") (pintype "passive"))
      (node (ref "SPI") (pin "6") (pinfunction "6_6") (pintype "passive"))
      (node (ref "U1") (pin "2") (pinfunction "GND1_2_2") (pintype "passive"))
      (node (ref "U1") (pin "8") (pinfunction "GND1_8") (pintype "passive"))
    )
    (net (code "29") (name "/N$29") (class "Default")
      (node (ref "C_C0") (pin "1") (pinfunction "1_1") (pintype "passive"))
      (node (ref "R_C0") (pin "2") (pinfunction "2_2") (pintype "passive"))
      (node (ref "U2") (pin "26") (pinfunction "C0_26") (pintype "input"))
    )
    (net (code "30") (name "/S1") (class "Default")
      (node (ref "R_SGATE1") (pin "2") (pinfunction "2_2") (pintype "passive"))
      (node (ref "U2") (pin "25") (pinfunction "S1_25") (pintype "tri_state"))
    )
    (net (code "31") (name "/S2") (class "Default")
      (node (ref "R_SGATE2") (pin "2") (pinfunction "2_2") (pintype "passive"))
      (node (ref "U2") (pin "23") (pinfunction "S2_23") (pintype "tri_state"))
    )
    (net (code "32") (name "/S3") (class "Default")
      (node (ref "R_SGATE3") (pin "2") (pinfunction "2_2") (pintype "passive"))
      (node (ref "U2") (pin "21") (pinfunction "S3_21") (pintype "tri_state"))
    )
    (net (code "33") (name "/S4") (class "Default")
      (node (ref "R_SGATE4") (pin "2") (pinfunction "2_2") (pintype "passive"))
      (node (ref "U2") (pin "19") (pinfunction "S4_19") (pintype "tri_state"))
    )
    (net (code "34") (name "/S5") (class "Default")
      (node (ref "R_SGATE5") (pin "2") (pinfunction "2_2") (pintype "passive"))
      (node (ref "U2") (pin "17") (pinfunction "S5_17") (pintype "tri_state"))
    )
    (net (code "35") (name "/S6") (class "Default")
      (node (ref "R_SGATE6") (pin "2") (pinfunction "2_2") (pintype "passive"))
      (node (ref "U2") (pin "15") (pinfunction "S6_15") (pintype "tri_state"))
    )
    (net (code "36") (name "/S7") (class "Default")
      (node (ref "R_SGATE7") (pin "2") (pinfunction "2_2") (pintype "passive"))
      (node (ref "U2") (pin "13") (pinfunction "S7_13") (pintype "tri_state"))
    )
    (net (code "37") (name "/S8") (class "Default")
      (node (ref "R_SGATE8") (pin "2") (pinfunction "2_2") (pintype "passive"))
      (node (ref "U2") (pin "11") (pinfunction "S8_11") (pintype "tri_state"))
    )
    (net (code "38") (name "/S9") (class "Default")
      (node (ref "R_SGATE9") (pin "2") (pinfunction "2_2") (pintype "passive"))
      (node (ref "U2") (pin "9") (pinfunction "S9_9") (pintype "tri_state"))
    )
    (net (code "39") (name "/S10") (class "Default")
      (node (ref "R_SGATE10") (pin "2") (pinfunction "2_2") (pintype "passive"))
      (node (ref "U2") (pin "7") (pinfunction "S10_7") (pintype "tri_state"))
    )
    (net (code "40") (name "/S11") (class "Default")
      (node (ref "R_SGATE11") (pin "2") (pinfunction "2_2") (pintype "passive"))
      (node (ref "U2") (pin "5") (pinfunction "S11_5") (pintype "tri_state"))
    )
    (net (code "41") (name "/S12") (class "Default")
      (node (ref "R_SGATE12") (pin "2") (pinfunction "2_2") (pintype "passive"))
      (node (ref "U2") (pin "3") (pinfunction "S12_3") (pintype "tri_state"))
    )
    (net (code "42") (name "/SPI_CHIPSELECT") (class "Default")
      (node (ref "R_A2") (pin "2") (pinfunction "2_2") (pintype "passive"))
      (node (ref "SPI") (pin "3") (pinfunction "3_3") (pintype "passive"))
    )
    (net (code "43") (name "/SPI_CLOCK") (class "Default")
      (node (ref "R_A1") (pin "2") (pinfunction "2_2") (pintype "passive"))
      (node (ref "SPI") (pin "2") (pinfunction "2_2") (pintype "passive"))
    )
    (net (code "44") (name "/SPI_MASTERIN") (class "Default")
      (node (ref "R_A4") (pin "2") (pinfunction "2_2") (pintype "passive"))
      (node (ref "SPI") (pin "5") (pinfunction "5_5") (pintype "passive"))
    )
    (net (code "45") (name "/SPI_MASTEROUT") (class "Default")
      (node (ref "R_A3") (pin "2") (pinfunction "2_2") (pintype "passive"))
      (node (ref "SPI") (pin "4") (pinfunction "4_4") (pintype "passive"))
    )
    (net (code "46") (name "/V+_LTC") (class "Default")
      (node (ref "C_V+1") (pin "1") (pinfunction "1_1") (pintype "passive"))
      (node (ref "C_V+2") (pin "1") (pinfunction "1_1") (pintype "passive"))
      (node (ref "C_V+LTC") (pin "1") (pinfunction "1_1") (pintype "passive"))
      (node (ref "D1_V+") (pin "C") (pinfunction "C_C") (pintype "passive"))
      (node (ref "D2_V+") (pin "C") (pinfunction "C_C") (pintype "passive"))
      (node (ref "R_V+") (pin "2") (pinfunction "2_2") (pintype "passive"))
      (node (ref "SCHOTTKY_V+") (pin "C") (pinfunction "C_C") (pintype "passive"))
      (node (ref "V+_LTC") (pin "2") (pinfunction "2_2") (pintype "passive"))
    )
    (net (code "47") (name "/VREF") (class "Default")
      (node (ref "C_VREF") (pin "1") (pinfunction "1_1") (pintype "passive"))
      (node (ref "R_VTEMP1") (pin "2") (pinfunction "2_2") (pintype "passive"))
      (node (ref "R_VTEMP2") (pin "2") (pinfunction "2_2") (pintype "passive"))
      (node (ref "U2") (pin "31") (pinfunction "VREF_31") (pintype "output"))
    )
    (net (code "48") (name "/VREG") (class "Default")
      (node (ref "C_VDDHV1") (pin "1") (pinfunction "1_1") (pintype "passive"))
      (node (ref "C_VDDHV2") (pin "1") (pinfunction "1_1") (pintype "passive"))
      (node (ref "C_VREG") (pin "1") (pinfunction "1_1") (pintype "passive"))
      (node (ref "LED_VDDHV") (pin "A") (pinfunction "A_A") (pintype "passive"))
      (node (ref "R_B1.") (pin "2") (pinfunction "2_2") (pintype "passive"))
      (node (ref "R_B2.") (pin "2") (pinfunction "2_2") (pintype "passive"))
      (node (ref "R_B3.") (pin "2") (pinfunction "2_2") (pintype "passive"))
      (node (ref "R_B4.") (pin "2") (pinfunction "2_2") (pintype "passive"))
      (node (ref "R_GPIO1") (pin "2") (pinfunction "2_2") (pintype "passive"))
      (node (ref "R_GPIO2") (pin "2") (pinfunction "2_2") (pintype "passive"))
      (node (ref "R_VDD_VREG") (pin "1") (pinfunction "1_1") (pintype "passive"))
      (node (ref "R_WDTB") (pin "1") (pinfunction "1_1") (pintype "passive"))
      (node (ref "U1") (pin "10") (pinfunction "EN2_10") (pintype "input"))
      (node (ref "U1") (pin "16") (pinfunction "VDD2_16") (pintype "passive"))
      (node (ref "U2") (pin "32") (pinfunction "VREG_32") (pintype "power_in"))
    )
    (net (code "49") (name "0V") (class "Default")
      (node (ref "C_C0") (pin "2") (pinfunction "2_2") (pintype "passive"))
      (node (ref "C_CIN1") (pin "2") (pinfunction "2_2") (pintype "passive"))
      (node (ref "C_CIN10") (pin "2") (pinfunction "2_2") (pintype "passive"))
      (node (ref "C_CIN11") (pin "2") (pinfunction "2_2") (pintype "passive"))
      (node (ref "C_CIN12") (pin "2") (pinfunction "2_2") (pintype "passive"))
      (node (ref "C_CIN2") (pin "2") (pinfunction "2_2") (pintype "passive"))
      (node (ref "C_CIN3") (pin "2") (pinfunction "2_2") (pintype "passive"))
      (node (ref "C_CIN4") (pin "2") (pinfunction "2_2") (pintype "passive"))
      (node (ref "C_CIN5") (pin "2") (pinfunction "2_2") (pintype "passive"))
      (node (ref "C_CIN6") (pin "2") (pinfunction "2_2") (pintype "passive"))
      (node (ref "C_CIN7") (pin "2") (pinfunction "2_2") (pintype "passive"))
      (node (ref "C_CIN8") (pin "2") (pinfunction "2_2") (pintype "passive"))
      (node (ref "C_CIN9") (pin "2") (pinfunction "2_2") (pintype "passive"))
      (node (ref "C_V+1") (pin "2") (pinfunction "2_2") (pintype "passive"))
      (node (ref "C_V+2") (pin "2") (pinfunction "2_2") (pintype "passive"))
      (node (ref "C_V+LTC") (pin "2") (pinfunction "2_2") (pintype "passive"))
      (node (ref "C_VDDHV1") (pin "2") (pinfunction "2_2") (pintype "passive"))
      (node (ref "C_VDDHV2") (pin "2") (pinfunction "2_2") (pintype "passive"))
      (node (ref "C_VREF") (pin "2") (pinfunction "2_2") (pintype "passive"))
      (node (ref "C_VREG") (pin "2") (pinfunction "2_2") (pintype "passive"))
      (node (ref "C_VTEMP1") (pin "2") (pinfunction "2_2") (pintype "passive"))
      (node (ref "C_VTEMP2") (pin "2") (pinfunction "2_2") (pintype "passive"))
      (node (ref "D1_V+") (pin "A") (pinfunction "A_A") (pintype "passive"))
      (node (ref "D2_V+") (pin "A") (pinfunction "A_A") (pintype "passive"))
      (node (ref "F13") (pin "1") (pinfunction "1_1") (pintype "bidirectional"))
      (node (ref "GPIO1") (pin "1") (pinfunction "1_1") (pintype "passive"))
      (node (ref "GPIO2") (pin "1") (pinfunction "1_1") (pintype "passive"))
      (node (ref "ISODCDC") (pin "1") (pinfunction "KL_1") (pintype "passive"))
      (node (ref "NTC1") (pin "2") (pinfunction "KL_2") (pintype "passive"))
      (node (ref "NTC2") (pin "2") (pinfunction "KL_2") (pintype "passive"))
      (node (ref "R_C0") (pin "1") (pinfunction "1_1") (pintype "passive"))
      (node (ref "R_VDDHV") (pin "1") (pinfunction "1_1") (pintype "passive"))
      (node (ref "SCHOTTKY_V+") (pin "A") (pinfunction "A_A") (pintype "passive"))
      (node (ref "U1") (pin "15") (pinfunction "GND2_15") (pintype "passive"))
      (node (ref "U1") (pin "9") (pinfunction "GND2_2_9") (pintype "passive"))
      (node (ref "U2") (pin "27") (pinfunction "V-_27") (pintype "power_in"))
      (node (ref "U2") (pin "28") (pinfunction "NC_28") (pintype "passive"))
      (node (ref "U2") (pin "33") (pinfunction "TOS_33") (pintype "input"))
      (node (ref "U2") (pin "37") (pinfunction "A0_37") (pintype "input"))
      (node (ref "U2") (pin "38") (pinfunction "A1_38") (pintype "input"))
      (node (ref "U2") (pin "39") (pinfunction "A2_39") (pintype "input"))
      (node (ref "U2") (pin "40") (pinfunction "A3_40") (pintype "input"))
    )
    (net (code "50") (name "Net-(F0-Pad2)") (class "Default")
      (node (ref "F0") (pin "2") (pinfunction "2_2") (pintype "bidirectional"))
      (node (ref "RD1") (pin "1") (pinfunction "1_1") (pintype "passive"))
      (node (ref "RLED1") (pin "1") (pinfunction "1_1") (pintype "passive"))
      (node (ref "R_CIN0") (pin "1") (pinfunction "1_1") (pintype "passive"))
    )
    (net (code "51") (name "Net-(GPIO1-Pad3)") (class "Default")
      (node (ref "GPIO1") (pin "3") (pinfunction "3_3") (pintype "passive"))
      (node (ref "R_GPIO1") (pin "1") (pinfunction "1_1") (pintype "passive"))
    )
    (net (code "52") (name "Net-(GPIO2-Pad3)") (class "Default")
      (node (ref "GPIO2") (pin "3") (pinfunction "3_3") (pintype "passive"))
      (node (ref "R_GPIO2") (pin "1") (pinfunction "1_1") (pintype "passive"))
    )
    (net (code "53") (name "Net-(ISODCDCB-KL)") (class "Default")
      (node (ref "ISODCDC") (pin "2") (pinfunction "KL_2") (pintype "passive"))
      (node (ref "V+_LTC") (pin "3") (pinfunction "3_3") (pintype "passive"))
    )
    (net (code "54") (name "Net-(LED1-PadC)") (class "Default")
      (node (ref "LED1") (pin "C") (pinfunction "C_C") (pintype "passive"))
      (node (ref "RLED1") (pin "2") (pinfunction "2_2") (pintype "passive"))
    )
    (net (code "55") (name "Net-(LED2-PadC)") (class "Default")
      (node (ref "LED2") (pin "C") (pinfunction "C_C") (pintype "passive"))
      (node (ref "RLED2") (pin "2") (pinfunction "2_2") (pintype "passive"))
    )
    (net (code "56") (name "Net-(LED3-PadC)") (class "Default")
      (node (ref "LED3") (pin "C") (pinfunction "C_C") (pintype "passive"))
      (node (ref "RLED3") (pin "2") (pinfunction "2_2") (pintype "passive"))
    )
    (net (code "57") (name "Net-(LED4-PadC)") (class "Default")
      (node (ref "LED4") (pin "C") (pinfunction "C_C") (pintype "passive"))
      (node (ref "RLED4") (pin "2") (pinfunction "2_2") (pintype "passive"))
    )
    (net (code "58") (name "Net-(LED5-PadC)") (class "Default")
      (node (ref "LED5") (pin "C") (pinfunction "C_C") (pintype "passive"))
      (node (ref "RLED5") (pin "2") (pinfunction "2_2") (pintype "passive"))
    )
    (net (code "59") (name "Net-(LED6-PadC)") (class "Default")
      (node (ref "LED6") (pin "C") (pinfunction "C_C") (pintype "passive"))
      (node (ref "RLED6") (pin "2") (pinfunction "2_2") (pintype "passive"))
    )
    (net (code "60") (name "Net-(LED7-PadC)") (class "Default")
      (node (ref "LED7") (pin "C") (pinfunction "C_C") (pintype "passive"))
      (node (ref "RLED7") (pin "2") (pinfunction "2_2") (pintype "passive"))
    )
    (net (code "61") (name "Net-(LED8-PadC)") (class "Default")
      (node (ref "LED8") (pin "C") (pinfunction "C_C") (pintype "passive"))
      (node (ref "RLED8") (pin "2") (pinfunction "2_2") (pintype "passive"))
    )
    (net (code "62") (name "Net-(LED9-PadC)") (class "Default")
      (node (ref "LED9") (pin "C") (pinfunction "C_C") (pintype "passive"))
      (node (ref "RLED9") (pin "2") (pinfunction "2_2") (pintype "passive"))
    )
    (net (code "63") (name "Net-(LED10-PadC)") (class "Default")
      (node (ref "LED10") (pin "C") (pinfunction "C_C") (pintype "passive"))
      (node (ref "RLED10") (pin "2") (pinfunction "2_2") (pintype "passive"))
    )
    (net (code "64") (name "Net-(LED11-PadC)") (class "Default")
      (node (ref "LED11") (pin "C") (pinfunction "C_C") (pintype "passive"))
      (node (ref "RLED11") (pin "2") (pinfunction "2_2") (pintype "passive"))
    )
    (net (code "65") (name "Net-(LED12-PadC)") (class "Default")
      (node (ref "LED12") (pin "C") (pinfunction "C_C") (pintype "passive"))
      (node (ref "RLED12") (pin "2") (pinfunction "2_2") (pintype "passive"))
    )
    (net (code "66") (name "Net-(LED_VDDHOST-PadC)") (class "Default")
      (node (ref "LED_VDDHOST") (pin "C") (pinfunction "C_C") (pintype "passive"))
      (node (ref "R_VDDHOST") (pin "2") (pinfunction "2_2") (pintype "passive"))
    )
    (net (code "67") (name "Net-(LED_VDDHV-PadC)") (class "Default")
      (node (ref "LED_VDDHV") (pin "C") (pinfunction "C_C") (pintype "passive"))
      (node (ref "R_VDDHV") (pin "2") (pinfunction "2_2") (pintype "passive"))
    )
    (net (code "68") (name "Net-(NTC1A-KL)") (class "Default")
      (node (ref "C_VTEMP1") (pin "1") (pinfunction "1_1") (pintype "passive"))
      (node (ref "NTC1") (pin "1") (pinfunction "KL_1") (pintype "passive"))
      (node (ref "R_VTEMP1") (pin "1") (pinfunction "1_1") (pintype "passive"))
      (node (ref "U2") (pin "29") (pinfunction "VTEMP1_29") (pintype "input"))
    )
    (net (code "69") (name "Net-(NTC2A-KL)") (class "Default")
      (node (ref "C_VTEMP2") (pin "1") (pinfunction "1_1") (pintype "passive"))
      (node (ref "NTC2") (pin "1") (pinfunction "KL_1") (pintype "passive"))
      (node (ref "R_VTEMP2") (pin "1") (pinfunction "1_1") (pintype "passive"))
      (node (ref "U2") (pin "30") (pinfunction "VTEMP2_30") (pintype "input"))
    )
    (net (code "70") (name "Net-(PMOS1-D)") (class "Default")
      (node (ref "LED1") (pin "A") (pinfunction "A_A") (pintype "passive"))
      (node (ref "PMOS1") (pin "3") (pinfunction "D_3") (pintype "bidirectional"))
      (node (ref "RD1") (pin "2") (pinfunction "2_2") (pintype "passive"))
    )
    (net (code "71") (name "Net-(PMOS1-G)") (class "Default")
      (node (ref "PMOS1") (pin "1") (pinfunction "G_1") (pintype "bidirectional"))
      (node (ref "R_SGATE1") (pin "1") (pinfunction "1_1") (pintype "passive"))
    )
    (net (code "72") (name "Net-(PMOS1-S)") (class "Default")
      (node (ref "F1") (pin "2") (pinfunction "2_2") (pintype "bidirectional"))
      (node (ref "PMOS1") (pin "2") (pinfunction "S_2") (pintype "bidirectional"))
      (node (ref "RD2") (pin "1") (pinfunction "1_1") (pintype "passive"))
      (node (ref "RLED2") (pin "1") (pinfunction "1_1") (pintype "passive"))
      (node (ref "R_CIN1") (pin "1") (pinfunction "1_1") (pintype "passive"))
    )
    (net (code "73") (name "Net-(PMOS2-D)") (class "Default")
      (node (ref "LED2") (pin "A") (pinfunction "A_A") (pintype "passive"))
      (node (ref "PMOS2") (pin "3") (pinfunction "D_3") (pintype "bidirectional"))
      (node (ref "RD2") (pin "2") (pinfunction "2_2") (pintype "passive"))
    )
    (net (code "74") (name "Net-(PMOS2-G)") (class "Default")
      (node (ref "PMOS2") (pin "1") (pinfunction "G_1") (pintype "bidirectional"))
      (node (ref "R_SGATE2") (pin "1") (pinfunction "1_1") (pintype "passive"))
    )
    (net (code "75") (name "Net-(PMOS2-S)") (class "Default")
      (node (ref "F2") (pin "2") (pinfunction "2_2") (pintype "bidirectional"))
      (node (ref "PMOS2") (pin "2") (pinfunction "S_2") (pintype "bidirectional"))
      (node (ref "RD3") (pin "1") (pinfunction "1_1") (pintype "passive"))
      (node (ref "RLED3") (pin "1") (pinfunction "1_1") (pintype "passive"))
      (node (ref "R_CIN2") (pin "1") (pinfunction "1_1") (pintype "passive"))
    )
    (net (code "76") (name "Net-(PMOS3-D)") (class "Default")
      (node (ref "LED3") (pin "A") (pinfunction "A_A") (pintype "passive"))
      (node (ref "PMOS3") (pin "3") (pinfunction "D_3") (pintype "bidirectional"))
      (node (ref "RD3") (pin "2") (pinfunction "2_2") (pintype "passive"))
    )
    (net (code "77") (name "Net-(PMOS3-G)") (class "Default")
      (node (ref "PMOS3") (pin "1") (pinfunction "G_1") (pintype "bidirectional"))
      (node (ref "R_SGATE3") (pin "1") (pinfunction "1_1") (pintype "passive"))
    )
    (net (code "78") (name "Net-(PMOS3-S)") (class "Default")
      (node (ref "F3") (pin "2") (pinfunction "2_2") (pintype "bidirectional"))
      (node (ref "PMOS3") (pin "2") (pinfunction "S_2") (pintype "bidirectional"))
      (node (ref "RD4") (pin "1") (pinfunction "1_1") (pintype "passive"))
      (node (ref "RLED4") (pin "1") (pinfunction "1_1") (pintype "passive"))
      (node (ref "R_CIN3") (pin "1") (pinfunction "1_1") (pintype "passive"))
    )
    (net (code "79") (name "Net-(PMOS4-D)") (class "Default")
      (node (ref "LED4") (pin "A") (pinfunction "A_A") (pintype "passive"))
      (node (ref "PMOS4") (pin "3") (pinfunction "D_3") (pintype "bidirectional"))
      (node (ref "RD4") (pin "2") (pinfunction "2_2") (pintype "passive"))
    )
    (net (code "80") (name "Net-(PMOS4-G)") (class "Default")
      (node (ref "PMOS4") (pin "1") (pinfunction "G_1") (pintype "bidirectional"))
      (node (ref "R_SGATE4") (pin "1") (pinfunction "1_1") (pintype "passive"))
    )
    (net (code "81") (name "Net-(PMOS4-S)") (class "Default")
      (node (ref "F4") (pin "2") (pinfunction "2_2") (pintype "bidirectional"))
      (node (ref "PMOS4") (pin "2") (pinfunction "S_2") (pintype "bidirectional"))
      (node (ref "RD5") (pin "1") (pinfunction "1_1") (pintype "passive"))
      (node (ref "RLED5") (pin "1") (pinfunction "1_1") (pintype "passive"))
      (node (ref "R_CIN4") (pin "1") (pinfunction "1_1") (pintype "passive"))
    )
    (net (code "82") (name "Net-(PMOS5-D)") (class "Default")
      (node (ref "LED5") (pin "A") (pinfunction "A_A") (pintype "passive"))
      (node (ref "PMOS5") (pin "3") (pinfunction "D_3") (pintype "bidirectional"))
      (node (ref "RD5") (pin "2") (pinfunction "2_2") (pintype "passive"))
    )
    (net (code "83") (name "Net-(PMOS5-G)") (class "Default")
      (node (ref "PMOS5") (pin "1") (pinfunction "G_1") (pintype "bidirectional"))
      (node (ref "R_SGATE5") (pin "1") (pinfunction "1_1") (pintype "passive"))
    )
    (net (code "84") (name "Net-(PMOS5-S)") (class "Default")
      (node (ref "F5") (pin "2") (pinfunction "2_2") (pintype "bidirectional"))
      (node (ref "PMOS5") (pin "2") (pinfunction "S_2") (pintype "bidirectional"))
      (node (ref "RD6") (pin "1") (pinfunction "1_1") (pintype "passive"))
      (node (ref "RLED6") (pin "1") (pinfunction "1_1") (pintype "passive"))
      (node (ref "R_CIN5") (pin "1") (pinfunction "1_1") (pintype "passive"))
    )
    (net (code "85") (name "Net-(PMOS6-D)") (class "Default")
      (node (ref "LED6") (pin "A") (pinfunction "A_A") (pintype "passive"))
      (node (ref "PMOS6") (pin "3") (pinfunction "D_3") (pintype "bidirectional"))
      (node (ref "RD6") (pin "2") (pinfunction "2_2") (pintype "passive"))
    )
    (net (code "86") (name "Net-(PMOS6-G)") (class "Default")
      (node (ref "PMOS6") (pin "1") (pinfunction "G_1") (pintype "bidirectional"))
      (node (ref "R_SGATE6") (pin "1") (pinfunction "1_1") (pintype "passive"))
    )
    (net (code "87") (name "Net-(PMOS6-S)") (class "Default")
      (node (ref "F6") (pin "2") (pinfunction "2_2") (pintype "bidirectional"))
      (node (ref "PMOS6") (pin "2") (pinfunction "S_2") (pintype "bidirectional"))
      (node (ref "RD7") (pin "1") (pinfunction "1_1") (pintype "passive"))
      (node (ref "RLED7") (pin "1") (pinfunction "1_1") (pintype "passive"))
      (node (ref "R_CIN6") (pin "1") (pinfunction "1_1") (pintype "passive"))
    )
    (net (code "88") (name "Net-(PMOS7-D)") (class "Default")
      (node (ref "LED7") (pin "A") (pinfunction "A_A") (pintype "passive"))
      (node (ref "PMOS7") (pin "3") (pinfunction "D_3") (pintype "bidirectional"))
      (node (ref "RD7") (pin "2") (pinfunction "2_2") (pintype "passive"))
    )
    (net (code "89") (name "Net-(PMOS7-G)") (class "Default")
      (node (ref "PMOS7") (pin "1") (pinfunction "G_1") (pintype "bidirectional"))
      (node (ref "R_SGATE7") (pin "1") (pinfunction "1_1") (pintype "passive"))
    )
    (net (code "90") (name "Net-(PMOS7-S)") (class "Default")
      (node (ref "F7") (pin "2") (pinfunction "2_2") (pintype "bidirectional"))
      (node (ref "PMOS7") (pin "2") (pinfunction "S_2") (pintype "bidirectional"))
      (node (ref "RD8") (pin "1") (pinfunction "1_1") (pintype "passive"))
      (node (ref "RLED8") (pin "1") (pinfunction "1_1") (pintype "passive"))
      (node (ref "R_CIN7") (pin "1") (pinfunction "1_1") (pintype "passive"))
    )
    (net (code "91") (name "Net-(PMOS8-D)") (class "Default")
      (node (ref "LED8") (pin "A") (pinfunction "A_A") (pintype "passive"))
      (node (ref "PMOS8") (pin "3") (pinfunction "D_3") (pintype "bidirectional"))
      (node (ref "RD8") (pin "2") (pinfunction "2_2") (pintype "passive"))
    )
    (net (code "92") (name "Net-(PMOS8-G)") (class "Default")
      (node (ref "PMOS8") (pin "1") (pinfunction "G_1") (pintype "bidirectional"))
      (node (ref "R_SGATE8") (pin "1") (pinfunction "1_1") (pintype "passive"))
    )
    (net (code "93") (name "Net-(PMOS8-S)") (class "Default")
      (node (ref "F8") (pin "2") (pinfunction "2_2") (pintype "bidirectional"))
      (node (ref "PMOS8") (pin "2") (pinfunction "S_2") (pintype "bidirectional"))
      (node (ref "RD9") (pin "1") (pinfunction "1_1") (pintype "passive"))
      (node (ref "RLED9") (pin "1") (pinfunction "1_1") (pintype "passive"))
      (node (ref "R_CIN8") (pin "1") (pinfunction "1_1") (pintype "passive"))
    )
    (net (code "94") (name "Net-(PMOS9-D)") (class "Default")
      (node (ref "LED9") (pin "A") (pinfunction "A_A") (pintype "passive"))
      (node (ref "PMOS9") (pin "3") (pinfunction "D_3") (pintype "bidirectional"))
      (node (ref "RD9") (pin "2") (pinfunction "2_2") (pintype "passive"))
    )
    (net (code "95") (name "Net-(PMOS9-G)") (class "Default")
      (node (ref "PMOS9") (pin "1") (pinfunction "G_1") (pintype "bidirectional"))
      (node (ref "R_SGATE9") (pin "1") (pinfunction "1_1") (pintype "passive"))
    )
    (net (code "96") (name "Net-(PMOS9-S)") (class "Default")
      (node (ref "F9") (pin "2") (pinfunction "2_2") (pintype "bidirectional"))
      (node (ref "PMOS9") (pin "2") (pinfunction "S_2") (pintype "bidirectional"))
      (node (ref "RD10") (pin "1") (pinfunction "1_1") (pintype "passive"))
      (node (ref "RLED10") (pin "1") (pinfunction "1_1") (pintype "passive"))
      (node (ref "R_CIN9") (pin "1") (pinfunction "1_1") (pintype "passive"))
    )
    (net (code "97") (name "Net-(PMOS10-D)") (class "Default")
      (node (ref "LED10") (pin "A") (pinfunction "A_A") (pintype "passive"))
      (node (ref "PMOS10") (pin "3") (pinfunction "D_3") (pintype "bidirectional"))
      (node (ref "RD10") (pin "2") (pinfunction "2_2") (pintype "passive"))
    )
    (net (code "98") (name "Net-(PMOS10-G)") (class "Default")
      (node (ref "PMOS10") (pin "1") (pinfunction "G_1") (pintype "bidirectional"))
      (node (ref "R_SGATE10") (pin "1") (pinfunction "1_1") (pintype "passive"))
    )
    (net (code "99") (name "Net-(PMOS10-S)") (class "Default")
      (node (ref "F10") (pin "2") (pinfunction "2_2") (pintype "bidirectional"))
      (node (ref "PMOS10") (pin "2") (pinfunction "S_2") (pintype "bidirectional"))
      (node (ref "RD11") (pin "1") (pinfunction "1_1") (pintype "passive"))
      (node (ref "RLED11") (pin "1") (pinfunction "1_1") (pintype "passive"))
      (node (ref "R_CIN10") (pin "1") (pinfunction "1_1") (pintype "passive"))
    )
    (net (code "100") (name "Net-(PMOS11-D)") (class "Default")
      (node (ref "LED11") (pin "A") (pinfunction "A_A") (pintype "passive"))
      (node (ref "PMOS11") (pin "3") (pinfunction "D_3") (pintype "bidirectional"))
      (node (ref "RD11") (pin "2") (pinfunction "2_2") (pintype "passive"))
    )
    (net (code "101") (name "Net-(PMOS11-G)") (class "Default")
      (node (ref "PMOS11") (pin "1") (pinfunction "G_1") (pintype "bidirectional"))
      (node (ref "R_SGATE11") (pin "1") (pinfunction "1_1") (pintype "passive"))
    )
    (net (code "102") (name "Net-(PMOS11-S)") (class "Default")
      (node (ref "F11") (pin "2") (pinfunction "2_2") (pintype "bidirectional"))
      (node (ref "PMOS11") (pin "2") (pinfunction "S_2") (pintype "bidirectional"))
      (node (ref "RD12") (pin "1") (pinfunction "1_1") (pintype "passive"))
      (node (ref "RLED12") (pin "1") (pinfunction "1_1") (pintype "passive"))
      (node (ref "R_CIN11") (pin "1") (pinfunction "1_1") (pintype "passive"))
    )
    (net (code "103") (name "Net-(PMOS12-D)") (class "Default")
      (node (ref "LED12") (pin "A") (pinfunction "A_A") (pintype "passive"))
      (node (ref "PMOS12") (pin "3") (pinfunction "D_3") (pintype "bidirectional"))
      (node (ref "RD12") (pin "2") (pinfunction "2_2") (pintype "passive"))
    )
    (net (code "104") (name "Net-(PMOS12-G)") (class "Default")
      (node (ref "PMOS12") (pin "1") (pinfunction "G_1") (pintype "bidirectional"))
      (node (ref "R_SGATE12") (pin "1") (pinfunction "1_1") (pintype "passive"))
    )
    (net (code "105") (name "Net-(PMOS12-S)") (class "Default")
      (node (ref "F12") (pin "2") (pinfunction "2_2") (pintype "bidirectional"))
      (node (ref "PMOS12") (pin "2") (pinfunction "S_2") (pintype "bidirectional"))
      (node (ref "R_CIN12") (pin "1") (pinfunction "1_1") (pintype "passive"))
    )
    (net (code "106") (name "Net-(U1-A1)") (class "Default")
      (node (ref "R_A1") (pin "1") (pinfunction "1_1") (pintype "passive"))
      (node (ref "U1") (pin "3") (pinfunction "A1_3") (pintype "input"))
    )
    (net (code "107") (name "Net-(U1-A2)") (class "Default")
      (node (ref "R_A2") (pin "1") (pinfunction "1_1") (pintype "passive"))
      (node (ref "U1") (pin "4") (pinfunction "A2_4") (pintype "input"))
    )
    (net (code "108") (name "Net-(U1-A3)") (class "Default")
      (node (ref "R_A3") (pin "1") (pinfunction "1_1") (pintype "passive"))
      (node (ref "U1") (pin "5") (pinfunction "A3_5") (pintype "input"))
    )
    (net (code "109") (name "Net-(U1-A4)") (class "Default")
      (node (ref "R_A4") (pin "1") (pinfunction "1_1") (pintype "passive"))
      (node (ref "U1") (pin "6") (pinfunction "A4_6") (pintype "output"))
    )
    (net (code "110") (name "Net-(U1-B1)") (class "Default")
      (node (ref "R_B1.") (pin "1") (pinfunction "1_1") (pintype "passive"))
      (node (ref "U1") (pin "14") (pinfunction "B1_14") (pintype "output"))
      (node (ref "U2") (pin "41") (pinfunction "SCKI_41") (pintype "input"))
    )
    (net (code "111") (name "Net-(U1-B2)") (class "Default")
      (node (ref "R_B2.") (pin "1") (pinfunction "1_1") (pintype "passive"))
      (node (ref "U1") (pin "13") (pinfunction "B2_13") (pintype "output"))
      (node (ref "U2") (pin "44") (pinfunction "CSBI_44") (pintype "input"))
    )
    (net (code "112") (name "Net-(U1-B3)") (class "Default")
      (node (ref "R_B3.") (pin "1") (pinfunction "1_1") (pintype "passive"))
      (node (ref "U1") (pin "12") (pinfunction "B3_12") (pintype "output"))
      (node (ref "U2") (pin "42") (pinfunction "SDI_42") (pintype "input"))
    )
    (net (code "113") (name "Net-(U1-B4)") (class "Default")
      (node (ref "R_B4.") (pin "1") (pinfunction "1_1") (pintype "passive"))
      (node (ref "R_VDD_VREG") (pin "2") (pinfunction "2_2") (pintype "passive"))
      (node (ref "U1") (pin "11") (pinfunction "B4_11") (pintype "input"))
      (node (ref "U2") (pin "43") (pinfunction "SDO_43") (pintype "open_collector"))
    )
    (net (code "114") (name "Net-(U2-GPIO1)") (class "Default")
      (node (ref "GPIO1") (pin "2") (pinfunction "2_2") (pintype "passive"))
      (node (ref "U2") (pin "35") (pinfunction "GPIO1_35") (pintype "bidirectional"))
    )
    (net (code "115") (name "Net-(U2-GPIO2)") (class "Default")
      (node (ref "GPIO2") (pin "2") (pinfunction "2_2") (pintype "passive"))
      (node (ref "U2") (pin "36") (pinfunction "GPIO2_36") (pintype "bidirectional"))
    )
    (net (code "116") (name "Net-(U2-V+)") (class "Default")
      (node (ref "R_V+") (pin "1") (pinfunction "1_1") (pintype "passive"))
      (node (ref "U2") (pin "1") (pinfunction "V+_1") (pintype "power_in"))
    )
    (net (code "117") (name "Net-(U2-WDTB)") (class "Default")
      (node (ref "R_WDTB") (pin "2") (pinfunction "2_2") (pintype "passive"))
      (node (ref "U2") (pin "34") (pinfunction "WDTB_34") (pintype "open_collector"))
    )
    (net (code "118") (name "unconnected-(X2F-KL-Pad6)") (class "Default")
      (node (ref "X2") (pin "6") (pinfunction "KL_6") (pintype "passive"))
    )
  )
)
